# brick_analog_led_green.net
KiCad netlist of a schematic drawn in EAGLE
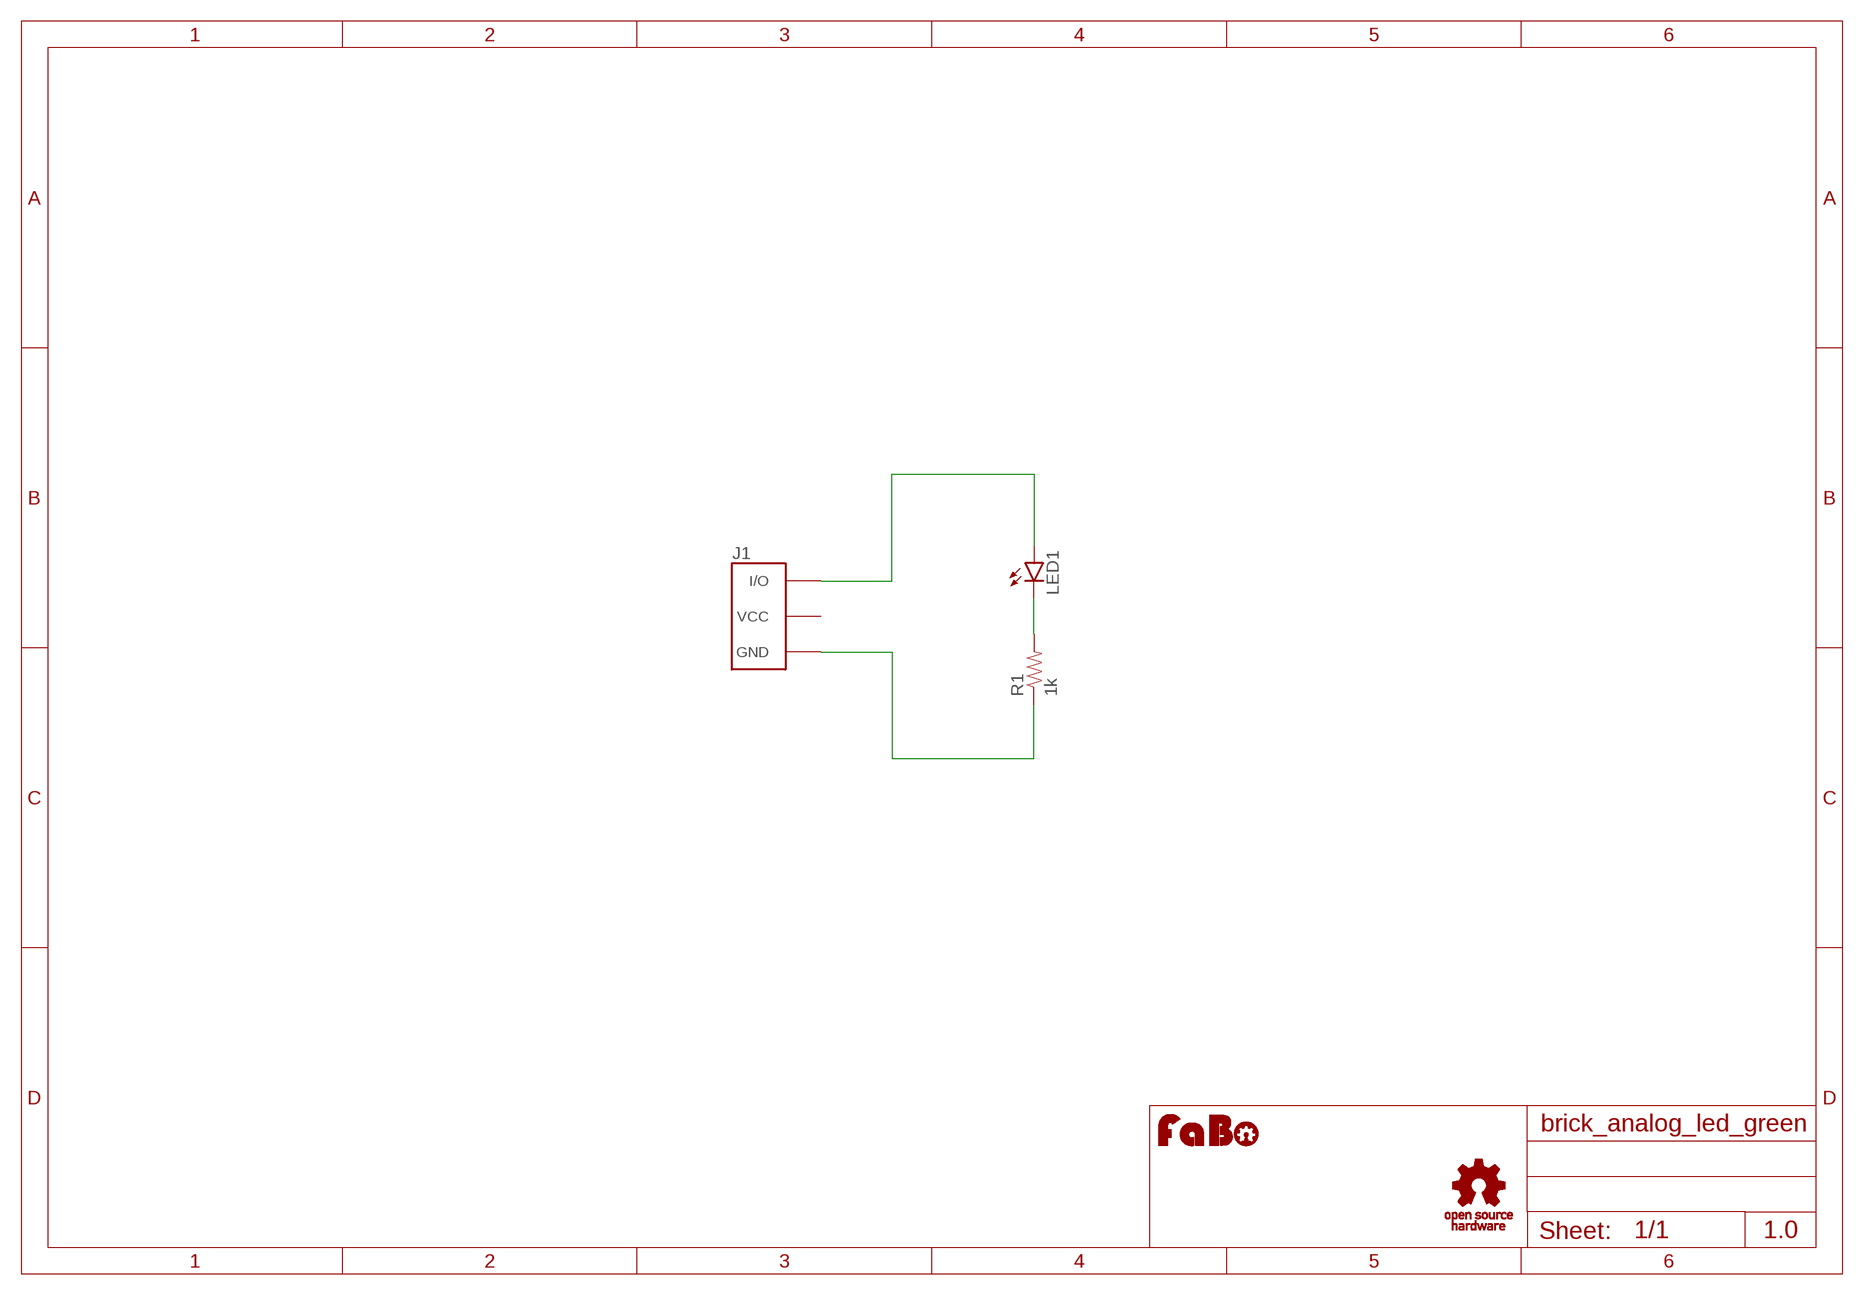
[diagram p0: schematic, sheet 1]

(export (version "E")
  (design (tool "Eeschema 10.0.6"))
  (components
    (comp (ref "J1")
      (value "BRICK_3PIN_NORMAL")
      (footprint "eagle-import:BRICK_3PIN")
      (libsource (lib "eagle-import") (part "BRICK_3PIN_NORMAL"))
    )
    (comp (ref "LED1")
      (value "LED-5MM")
      (footprint "eagle-import:LED-5MM")
      (libsource (lib "eagle-import") (part "LED-5MM"))
    )
    (comp (ref "R1")
      (value "1k")
      (footprint "eagle-import:RES-AXL-REGULAR")
      (libsource (lib "eagle-import") (part "RES-PTH-REGULAR"))
    )
    (comp (ref "U$1")
      (value "LOGO_FABO-M")
      (footprint "eagle-import:LOGO_FABO_M")
      (libsource (lib "eagle-import") (part "LOGO_FABO-M"))
    )
    (comp (ref "U$4")
      (value "LOGO_OSHW_T-M")
      (footprint "eagle-import:LOGO_OSHW_T_M")
      (libsource (lib "eagle-import") (part "LOGO_OSHW_T-M"))
    )
  )
  (nets
    (net (code "1") (name "Net-(J1-I{slash}O)") (class "Default")
      (node (ref "J1") (pin "IN/OUT") (pinfunction "I/O_IN/OUT") (pintype "bidirectional"))
      (node (ref "LED1") (pin "A") (pinfunction "A_A") (pintype "passive"))
    )
    (net (code "2") (name "Net-(LED1-C)") (class "Default")
      (node (ref "LED1") (pin "K") (pinfunction "C_K") (pintype "passive"))
      (node (ref "R1") (pin "P$2") (pinfunction "2_P$2") (pintype "passive"))
    )
    (net (code "3") (name "Net-(R1-1)") (class "Default")
      (node (ref "J1") (pin "GND") (pinfunction "GND_GND") (pintype "bidirectional"))
      (node (ref "R1") (pin "P$1") (pinfunction "1_P$1") (pintype "passive"))
    )
    (net (code "4") (name "unconnected-(J1-PadVCC)") (class "Default")
      (node (ref "J1") (pin "VCC") (pinfunction "VCC_VCC") (pintype "bidirectional"))
    )
  )
)
